# AnalogLedFader.net
KiCad netlist of a schematic drawn in EAGLE
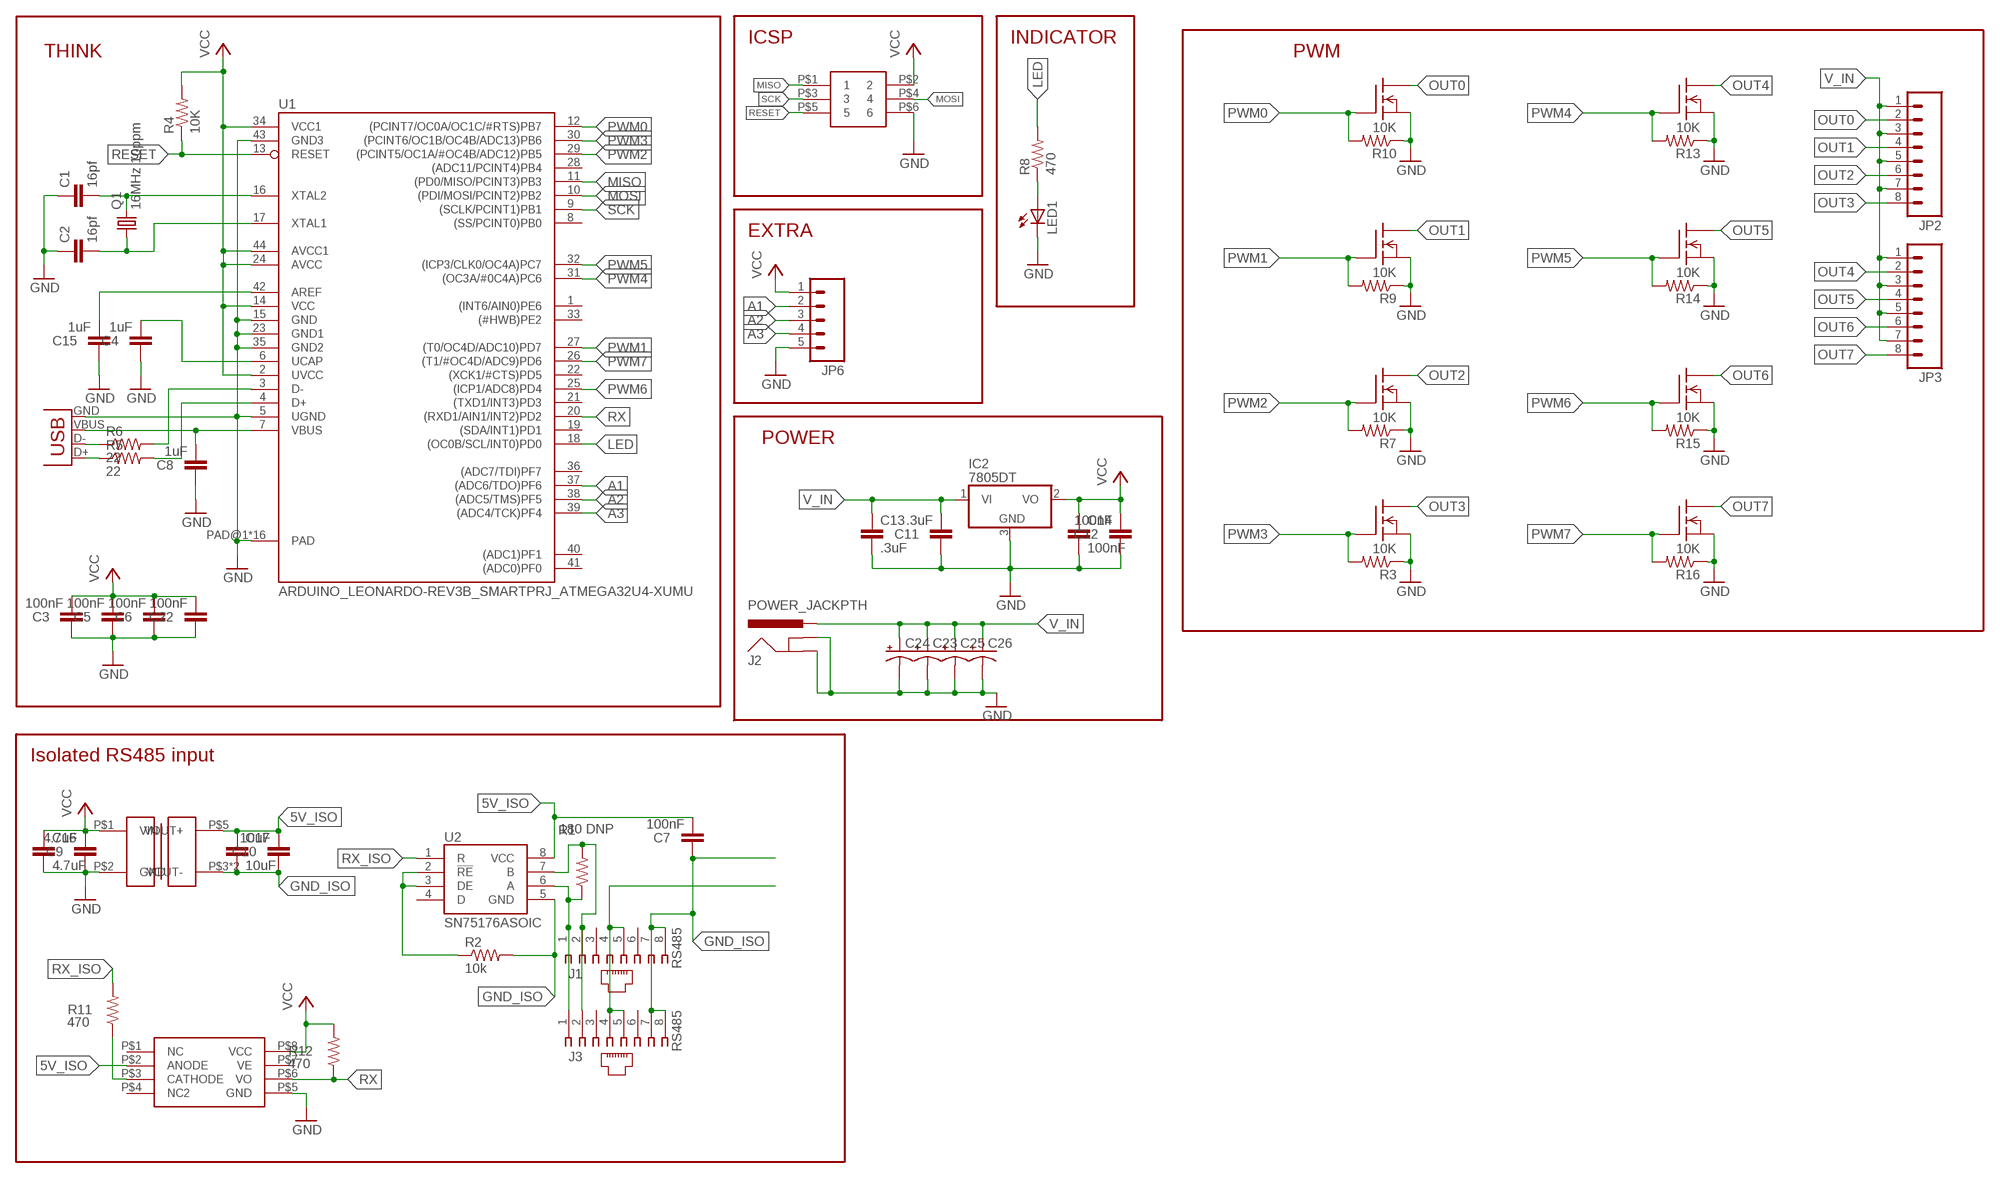
[diagram p0: schematic, sheet 1]

(export (version "E")
  (design (tool "Eeschema 10.0.6"))
  (components
    (comp (ref "C1")
      (value "16pf")
      (footprint "eagle-import:0805")
      (libsource (lib "eagle-import") (part "CAP0805"))
    )
    (comp (ref "C2")
      (value "16pf")
      (footprint "eagle-import:0805")
      (libsource (lib "eagle-import") (part "CAP0805"))
    )
    (comp (ref "C3")
      (value "100nF")
      (footprint "eagle-import:0805")
      (libsource (lib "eagle-import") (part "CAP0805"))
    )
    (comp (ref "C4")
      (value "1uF")
      (footprint "eagle-import:0805")
      (libsource (lib "eagle-import") (part "CAP0805"))
    )
    (comp (ref "C5")
      (value "100nF")
      (footprint "eagle-import:0805")
      (libsource (lib "eagle-import") (part "CAP0805"))
    )
    (comp (ref "C6")
      (value "100nF")
      (footprint "eagle-import:0805")
      (libsource (lib "eagle-import") (part "CAP0805"))
    )
    (comp (ref "C7")
      (value "100nF")
      (footprint "eagle-import:0805")
      (libsource (lib "eagle-import") (part "CAP0805"))
    )
    (comp (ref "C8")
      (value "1uF")
      (footprint "eagle-import:0805")
      (libsource (lib "eagle-import") (part "CAP0805"))
    )
    (comp (ref "C9")
      (value "4.7uF")
      (footprint "eagle-import:0805")
      (libsource (lib "eagle-import") (part "CAP0805"))
    )
    (comp (ref "C10")
      (value "10uF")
      (footprint "eagle-import:0805")
      (libsource (lib "eagle-import") (part "CAP0805"))
    )
    (comp (ref "C11")
      (value ".3uF")
      (footprint "eagle-import:0805")
      (libsource (lib "eagle-import") (part "CAP0805"))
    )
    (comp (ref "C12")
      (value "100nF")
      (footprint "eagle-import:0805")
      (libsource (lib "eagle-import") (part "CAP0805"))
    )
    (comp (ref "C13")
      (value ".3uF")
      (footprint "eagle-import:1210")
      (libsource (lib "eagle-import") (part "CAP1210"))
    )
    (comp (ref "C14")
      (value "100nF")
      (footprint "eagle-import:1210")
      (libsource (lib "eagle-import") (part "CAP1210"))
    )
    (comp (ref "C15")
      (value "1uF")
      (footprint "eagle-import:0805")
      (libsource (lib "eagle-import") (part "CAP0805"))
    )
    (comp (ref "C16")
      (value "4.7uF")
      (footprint "eagle-import:1210")
      (libsource (lib "eagle-import") (part "CAP1210"))
    )
    (comp (ref "C17")
      (value "10uF")
      (footprint "eagle-import:1210")
      (libsource (lib "eagle-import") (part "CAP1210"))
    )
    (comp (ref "C22")
      (value "100nF")
      (footprint "eagle-import:0805")
      (libsource (lib "eagle-import") (part "CAP0805"))
    )
    (comp (ref "C23")
      (value "CAP_POLE")
      (footprint "eagle-import:PANASONIC_E")
      (libsource (lib "eagle-import") (part "CAP_POLE"))
    )
    (comp (ref "C24")
      (value "CAP_POLE")
      (footprint "eagle-import:PANASONIC_E")
      (libsource (lib "eagle-import") (part "CAP_POLE"))
    )
    (comp (ref "C25")
      (value "CAP_POLE")
      (footprint "eagle-import:PANASONIC_E")
      (libsource (lib "eagle-import") (part "CAP_POLE"))
    )
    (comp (ref "C26")
      (value "CAP_POLE")
      (footprint "eagle-import:PANASONIC_E")
      (libsource (lib "eagle-import") (part "CAP_POLE"))
    )
    (comp (ref "IC2")
      (value "7805DT")
      (footprint "eagle-import:TO252")
      (libsource (lib "eagle-import") (part "78DT05"))
    )
    (comp (ref "J1")
      (value "RS485")
      (footprint "eagle-import:520426-4")
      (libsource (lib "eagle-import") (part "520426-4"))
    )
    (comp (ref "J2")
      (value "POWER_JACKPTH")
      (footprint "eagle-import:POWER_JACK_PTH")
      (libsource (lib "eagle-import") (part "POWER_JACKPTH"))
    )
    (comp (ref "J3")
      (value "RS485")
      (footprint "eagle-import:520426-4")
      (libsource (lib "eagle-import") (part "520426-4"))
    )
    (comp (ref "JP2")
      (value "M083.5MM-8")
      (footprint "eagle-import:SCREWTERMINAL-3.5MM-8")
      (libsource (lib "eagle-import") (part "M083.5MM-8"))
    )
    (comp (ref "JP3")
      (value "M083.5MM-8")
      (footprint "eagle-import:SCREWTERMINAL-3.5MM-8")
      (libsource (lib "eagle-import") (part "M083.5MM-8"))
    )
    (comp (ref "JP6")
      (value "M05PTH")
      (footprint "eagle-import:1X05")
      (libsource (lib "eagle-import") (part "M05PTH"))
    )
    (comp (ref "LED1")
      (value "LED5MM")
      (footprint "eagle-import:LED5MM")
      (libsource (lib "eagle-import") (part "LED5MM"))
    )
    (comp (ref "Q1")
      (value "16MHz 10ppm")
      (footprint "eagle-import:XS3225")
      (libsource (lib "eagle-import") (part "CRYSTAL"))
    )
    (comp (ref "R1")
      (value "180 DNP")
      (footprint "eagle-import:0805")
      (libsource (lib "eagle-import") (part "RESISTOR"))
    )
    (comp (ref "R2")
      (value "10k")
      (footprint "eagle-import:0805")
      (libsource (lib "eagle-import") (part "RESISTOR"))
    )
    (comp (ref "R3")
      (value "10K")
      (footprint "eagle-import:0805")
      (libsource (lib "eagle-import") (part "RESISTOR"))
    )
    (comp (ref "R4")
      (value "10K")
      (footprint "eagle-import:0805")
      (libsource (lib "eagle-import") (part "RESISTOR"))
    )
    (comp (ref "R5")
      (value "22")
      (footprint "eagle-import:0805")
      (libsource (lib "eagle-import") (part "RESISTOR"))
    )
    (comp (ref "R6")
      (value "22")
      (footprint "eagle-import:0805")
      (libsource (lib "eagle-import") (part "RESISTOR"))
    )
    (comp (ref "R7")
      (value "10K")
      (footprint "eagle-import:0805")
      (libsource (lib "eagle-import") (part "RESISTOR"))
    )
    (comp (ref "R8")
      (value "470")
      (footprint "eagle-import:0805")
      (libsource (lib "eagle-import") (part "RESISTOR"))
    )
    (comp (ref "R9")
      (value "10K")
      (footprint "eagle-import:0805")
      (libsource (lib "eagle-import") (part "RESISTOR"))
    )
    (comp (ref "R10")
      (value "10K")
      (footprint "eagle-import:0805")
      (libsource (lib "eagle-import") (part "RESISTOR"))
    )
    (comp (ref "R11")
      (value "470")
      (footprint "eagle-import:0805")
      (libsource (lib "eagle-import") (part "RESISTOR"))
    )
    (comp (ref "R12")
      (value "470")
      (footprint "eagle-import:0805")
      (libsource (lib "eagle-import") (part "RESISTOR"))
    )
    (comp (ref "R13")
      (value "10K")
      (footprint "eagle-import:0805")
      (libsource (lib "eagle-import") (part "RESISTOR"))
    )
    (comp (ref "R14")
      (value "10K")
      (footprint "eagle-import:0805")
      (libsource (lib "eagle-import") (part "RESISTOR"))
    )
    (comp (ref "R15")
      (value "10K")
      (footprint "eagle-import:0805")
      (libsource (lib "eagle-import") (part "RESISTOR"))
    )
    (comp (ref "R16")
      (value "10K")
      (footprint "eagle-import:0805")
      (libsource (lib "eagle-import") (part "RESISTOR"))
    )
    (comp (ref "U$1")
      (value "N_MOSFET")
      (footprint "eagle-import:TO252")
      (libsource (lib "eagle-import") (part "N_MOSFET"))
    )
    (comp (ref "U$2")
      (value "2X3HEADER")
      (footprint "eagle-import:2X3HEADER")
      (libsource (lib "eagle-import") (part "2X3HEADER"))
    )
    (comp (ref "U$3")
      (value "N_MOSFET")
      (footprint "eagle-import:TO252")
      (libsource (lib "eagle-import") (part "N_MOSFET"))
    )
    (comp (ref "U$4")
      (value "N_MOSFET")
      (footprint "eagle-import:TO252")
      (libsource (lib "eagle-import") (part "N_MOSFET"))
    )
    (comp (ref "U$5")
      (value "N_MOSFET")
      (footprint "eagle-import:TO252")
      (libsource (lib "eagle-import") (part "N_MOSFET"))
    )
    (comp (ref "U$6")
      (value "N_MOSFET")
      (footprint "eagle-import:TO252")
      (libsource (lib "eagle-import") (part "N_MOSFET"))
    )
    (comp (ref "U$7")
      (value "N_MOSFET")
      (footprint "eagle-import:TO252")
      (libsource (lib "eagle-import") (part "N_MOSFET"))
    )
    (comp (ref "U$8")
      (value "N_MOSFET")
      (footprint "eagle-import:TO252")
      (libsource (lib "eagle-import") (part "N_MOSFET"))
    )
    (comp (ref "U$9")
      (value "N_MOSFET")
      (footprint "eagle-import:TO252")
      (libsource (lib "eagle-import") (part "N_MOSFET"))
    )
    (comp (ref "U$10")
      (value "DC_DC_ISOLATED_0505")
      (footprint "eagle-import:IB_XLS-1W")
      (libsource (lib "eagle-import") (part "DC_DC_ISOLATED_0505"))
    )
    (comp (ref "U$12")
      (value "6N137")
      (footprint "eagle-import:8_SOIC")
      (libsource (lib "eagle-import") (part "6N137"))
    )
    (comp (ref "U1")
      (value "ARDUINO_LEONARDO-REV3B_SMARTPRJ_ATMEGA32U4-XUMU")
      (footprint "eagle-import:ARDUINO_LEONARDO-REV3B_SMARTPRJ_QFN44ML7X7")
      (libsource (lib "eagle-import") (part "ARDUINO_LEONARDO-REV3B_SMARTPRJ_ATMEGA32U4-XUMU"))
    )
    (comp (ref "U2")
      (value "SN75176ASOIC")
      (footprint "eagle-import:SO08")
      (libsource (lib "eagle-import") (part "SN75176ASOIC"))
    )
    (comp (ref "X1")
      (value "USBPTH")
      (footprint "eagle-import:USB-B-PTH")
      (libsource (lib "eagle-import") (part "USBPTH"))
    )
  )
  (nets
    (net (code "1") (name "5V_ISO") (class "Default")
      (node (ref "C10") (pin "2") (pinfunction "2_2") (pintype "passive"))
      (node (ref "C17") (pin "1") (pinfunction "1_1") (pintype "passive"))
      (node (ref "C7") (pin "2") (pinfunction "2_2") (pintype "passive"))
      (node (ref "U$10") (pin "P$5") (pinfunction "VOUT+_P$5") (pintype "power_in"))
      (node (ref "U$12") (pin "P$2") (pinfunction "ANODE_P$2") (pintype "bidirectional"))
      (node (ref "U2") (pin "8") (pinfunction "VCC_8") (pintype "bidirectional"))
    )
    (net (code "2") (name "A1") (class "Default")
      (node (ref "JP6") (pin "2") (pinfunction "2_2") (pintype "passive"))
      (node (ref "U1") (pin "37") (pinfunction "(ADC6/TDO)PF6_37") (pintype "bidirectional"))
    )
    (net (code "3") (name "A2") (class "Default")
      (node (ref "JP6") (pin "3") (pinfunction "3_3") (pintype "passive"))
      (node (ref "U1") (pin "38") (pinfunction "(ADC5/TMS)PF5_38") (pintype "bidirectional"))
    )
    (net (code "4") (name "A3") (class "Default")
      (node (ref "JP6") (pin "4") (pinfunction "4_4") (pintype "passive"))
      (node (ref "U1") (pin "39") (pinfunction "(ADC4/TCK)PF4_39") (pintype "bidirectional"))
    )
    (net (code "5") (name "GND") (class "Default")
      (node (ref "C1") (pin "1") (pinfunction "1_1") (pintype "passive"))
      (node (ref "C11") (pin "1") (pinfunction "1_1") (pintype "passive"))
      (node (ref "C12") (pin "1") (pinfunction "1_1") (pintype "passive"))
      (node (ref "C13") (pin "2") (pinfunction "2_2") (pintype "passive"))
      (node (ref "C14") (pin "2") (pinfunction "2_2") (pintype "passive"))
      (node (ref "C15") (pin "1") (pinfunction "1_1") (pintype "passive"))
      (node (ref "C16") (pin "2") (pinfunction "2_2") (pintype "passive"))
      (node (ref "C2") (pin "1") (pinfunction "1_1") (pintype "passive"))
      (node (ref "C22") (pin "1") (pinfunction "1_1") (pintype "passive"))
      (node (ref "C23") (pin "-") (pinfunction "-_-") (pintype "passive"))
      (node (ref "C24") (pin "-") (pinfunction "-_-") (pintype "passive"))
      (node (ref "C25") (pin "-") (pinfunction "-_-") (pintype "passive"))
      (node (ref "C26") (pin "-") (pinfunction "-_-") (pintype "passive"))
      (node (ref "C3") (pin "1") (pinfunction "1_1") (pintype "passive"))
      (node (ref "C4") (pin "1") (pinfunction "1_1") (pintype "passive"))
      (node (ref "C5") (pin "1") (pinfunction "1_1") (pintype "passive"))
      (node (ref "C6") (pin "1") (pinfunction "1_1") (pintype "passive"))
      (node (ref "C8") (pin "1") (pinfunction "1_1") (pintype "passive"))
      (node (ref "C9") (pin "1") (pinfunction "1_1") (pintype "passive"))
      (node (ref "IC2") (pin "3") (pinfunction "GND_3") (pintype "passive"))
      (node (ref "J2") (pin "GND") (pinfunction "GND_GND") (pintype "bidirectional"))
      (node (ref "J2") (pin "GNDBREAK") (pinfunction "GNDBREAK_GNDBREAK") (pintype "bidirectional"))
      (node (ref "JP6") (pin "5") (pinfunction "5_5") (pintype "passive"))
      (node (ref "LED1") (pin "K") (pinfunction "C_K") (pintype "passive"))
      (node (ref "R10") (pin "1") (pinfunction "1_1") (pintype "passive"))
      (node (ref "R13") (pin "1") (pinfunction "1_1") (pintype "passive"))
      (node (ref "R14") (pin "1") (pinfunction "1_1") (pintype "passive"))
      (node (ref "R15") (pin "1") (pinfunction "1_1") (pintype "passive"))
      (node (ref "R16") (pin "1") (pinfunction "1_1") (pintype "passive"))
      (node (ref "R3") (pin "1") (pinfunction "1_1") (pintype "passive"))
      (node (ref "R7") (pin "1") (pinfunction "1_1") (pintype "passive"))
      (node (ref "R9") (pin "1") (pinfunction "1_1") (pintype "passive"))
      (node (ref "U$1") (pin "P$2") (pinfunction "S_P$2") (pintype "bidirectional"))
      (node (ref "U$10") (pin "P$2") (pinfunction "GND_P$2") (pintype "power_in"))
      (node (ref "U$12") (pin "P$5") (pinfunction "GND_P$5") (pintype "bidirectional"))
      (node (ref "U$2") (pin "P$6") (pinfunction "6_P$6") (pintype "bidirectional"))
      (node (ref "U$3") (pin "P$2") (pinfunction "S_P$2") (pintype "bidirectional"))
      (node (ref "U$4") (pin "P$2") (pinfunction "S_P$2") (pintype "bidirectional"))
      (node (ref "U$5") (pin "P$2") (pinfunction "S_P$2") (pintype "bidirectional"))
      (node (ref "U$6") (pin "P$2") (pinfunction "S_P$2") (pintype "bidirectional"))
      (node (ref "U$7") (pin "P$2") (pinfunction "S_P$2") (pintype "bidirectional"))
      (node (ref "U$8") (pin "P$2") (pinfunction "S_P$2") (pintype "bidirectional"))
      (node (ref "U$9") (pin "P$2") (pinfunction "S_P$2") (pintype "bidirectional"))
      (node (ref "U1") (pin "15") (pinfunction "GND_15") (pintype "power_in"))
      (node (ref "U1") (pin "23") (pinfunction "GND1_23") (pintype "power_in"))
      (node (ref "U1") (pin "35") (pinfunction "GND2_35") (pintype "power_in"))
      (node (ref "U1") (pin "43") (pinfunction "GND3_43") (pintype "power_in"))
      (node (ref "U1") (pin "5") (pinfunction "UGND_5") (pintype "power_in"))
      (node (ref "U1") (pin "PAD@1") (pinfunction "PAD_PAD@1") (pintype "power_in"))
      (node (ref "U1") (pin "PAD@10") (pinfunction "PAD_PAD@10") (pintype "power_in"))
      (node (ref "U1") (pin "PAD@11") (pinfunction "PAD_PAD@11") (pintype "power_in"))
      (node (ref "U1") (pin "PAD@12") (pinfunction "PAD_PAD@12") (pintype "power_in"))
      (node (ref "U1") (pin "PAD@13") (pinfunction "PAD_PAD@13") (pintype "power_in"))
      (node (ref "U1") (pin "PAD@14") (pinfunction "PAD_PAD@14") (pintype "power_in"))
      (node (ref "U1") (pin "PAD@15") (pinfunction "PAD_PAD@15") (pintype "power_in"))
      (node (ref "U1") (pin "PAD@16") (pinfunction "PAD_PAD@16") (pintype "power_in"))
      (node (ref "U1") (pin "PAD@2") (pinfunction "PAD_PAD@2") (pintype "power_in"))
      (node (ref "U1") (pin "PAD@3") (pinfunction "PAD_PAD@3") (pintype "power_in"))
      (node (ref "U1") (pin "PAD@4") (pinfunction "PAD_PAD@4") (pintype "power_in"))
      (node (ref "U1") (pin "PAD@5") (pinfunction "PAD_PAD@5") (pintype "power_in"))
      (node (ref "U1") (pin "PAD@6") (pinfunction "PAD_PAD@6") (pintype "power_in"))
      (node (ref "U1") (pin "PAD@7") (pinfunction "PAD_PAD@7") (pintype "power_in"))
      (node (ref "U1") (pin "PAD@8") (pinfunction "PAD_PAD@8") (pintype "power_in"))
      (node (ref "U1") (pin "PAD@9") (pinfunction "PAD_PAD@9") (pintype "power_in"))
      (node (ref "X1") (pin "GND") (pinfunction "GND_GND") (pintype "bidirectional"))
    )
    (net (code "6") (name "GND_ISO") (class "Default")
      (node (ref "C10") (pin "1") (pinfunction "1_1") (pintype "passive"))
      (node (ref "C17") (pin "2") (pinfunction "2_2") (pintype "passive"))
      (node (ref "C7") (pin "1") (pinfunction "1_1") (pintype "passive"))
      (node (ref "J1") (pin "7") (pinfunction "7_7") (pintype "passive"))
      (node (ref "J1") (pin "8") (pinfunction "8_8") (pintype "passive"))
      (node (ref "J3") (pin "7") (pinfunction "7_7") (pintype "passive"))
      (node (ref "J3") (pin "8") (pinfunction "8_8") (pintype "passive"))
      (node (ref "R2") (pin "2") (pinfunction "2_2") (pintype "passive"))
      (node (ref "U$10") (pin "P$3") (pinfunction "VOUT-_P$3") (pintype "power_in"))
      (node (ref "U$10") (pin "P$4") (pinfunction "VOUT-_P$4") (pintype "power_in"))
      (node (ref "U2") (pin "5") (pinfunction "GND_5") (pintype "bidirectional"))
    )
    (net (code "7") (name "LED") (class "Default")
      (node (ref "R8") (pin "2") (pinfunction "2_2") (pintype "passive"))
      (node (ref "U1") (pin "18") (pinfunction "(OC0B/SCL/INT0)PD0_18") (pintype "bidirectional"))
    )
    (net (code "8") (name "MISO") (class "Default")
      (node (ref "U$2") (pin "P$1") (pinfunction "1_P$1") (pintype "bidirectional"))
      (node (ref "U1") (pin "11") (pinfunction "(PD0/MISO/PCINT3)PB3_11") (pintype "bidirectional"))
    )
    (net (code "9") (name "MOSI") (class "Default")
      (node (ref "U$2") (pin "P$4") (pinfunction "4_P$4") (pintype "bidirectional"))
      (node (ref "U1") (pin "10") (pinfunction "(PDI/MOSI/PCINT2)PB2_10") (pintype "bidirectional"))
    )
    (net (code "10") (name "Net-(J1-Pad4)") (class "Default")
      (node (ref "J1") (pin "4") (pinfunction "4_4") (pintype "passive"))
      (node (ref "J1") (pin "5") (pinfunction "5_5") (pintype "passive"))
      (node (ref "J3") (pin "4") (pinfunction "4_4") (pintype "passive"))
      (node (ref "J3") (pin "5") (pinfunction "5_5") (pintype "passive"))
    )
    (net (code "11") (name "Net-(LED1-PadA)") (class "Default")
      (node (ref "LED1") (pin "A") (pinfunction "A_A") (pintype "passive"))
      (node (ref "R8") (pin "1") (pinfunction "1_1") (pintype "passive"))
    )
    (net (code "12") (name "Net-(Q1-1)") (class "Default")
      (node (ref "C2") (pin "2") (pinfunction "2_2") (pintype "passive"))
      (node (ref "Q1") (pin "P$1") (pinfunction "1_P$1") (pintype "passive"))
      (node (ref "U1") (pin "17") (pinfunction "XTAL1_17") (pintype "bidirectional"))
    )
    (net (code "13") (name "Net-(Q1-2)") (class "Default")
      (node (ref "C1") (pin "2") (pinfunction "2_2") (pintype "passive"))
      (node (ref "Q1") (pin "P$3") (pinfunction "2_P$3") (pintype "passive"))
      (node (ref "U1") (pin "16") (pinfunction "XTAL2_16") (pintype "bidirectional"))
    )
    (net (code "14") (name "Net-(R5-Pad1)") (class "Default")
      (node (ref "R5") (pin "1") (pinfunction "1_1") (pintype "passive"))
      (node (ref "X1") (pin "D+") (pinfunction "D+_D+") (pintype "bidirectional"))
    )
    (net (code "15") (name "Net-(R6-Pad1)") (class "Default")
      (node (ref "R6") (pin "1") (pinfunction "1_1") (pintype "passive"))
      (node (ref "X1") (pin "D-") (pinfunction "D-_D-") (pintype "bidirectional"))
    )
    (net (code "16") (name "Net-(U$12-CATHODE)") (class "Default")
      (node (ref "R11") (pin "1") (pinfunction "1_1") (pintype "passive"))
      (node (ref "U$12") (pin "P$3") (pinfunction "CATHODE_P$3") (pintype "bidirectional"))
    )
    (net (code "17") (name "Net-(U1-AREF)") (class "Default")
      (node (ref "C15") (pin "2") (pinfunction "2_2") (pintype "passive"))
      (node (ref "U1") (pin "42") (pinfunction "AREF_42") (pintype "power_in"))
    )
    (net (code "18") (name "Net-(U1-D+)") (class "Default")
      (node (ref "R5") (pin "2") (pinfunction "2_2") (pintype "passive"))
      (node (ref "U1") (pin "4") (pinfunction "D+_4") (pintype "bidirectional"))
    )
    (net (code "19") (name "Net-(U1-D-)") (class "Default")
      (node (ref "R6") (pin "2") (pinfunction "2_2") (pintype "passive"))
      (node (ref "U1") (pin "3") (pinfunction "D-_3") (pintype "bidirectional"))
    )
    (net (code "20") (name "Net-(U1-UCAP)") (class "Default")
      (node (ref "C4") (pin "2") (pinfunction "2_2") (pintype "passive"))
      (node (ref "U1") (pin "6") (pinfunction "UCAP_6") (pintype "passive"))
    )
    (net (code "21") (name "Net-(U1-VBUS)") (class "Default")
      (node (ref "C8") (pin "2") (pinfunction "2_2") (pintype "passive"))
      (node (ref "U1") (pin "7") (pinfunction "VBUS_7") (pintype "input"))
      (node (ref "X1") (pin "VBUS") (pinfunction "VBUS_VBUS") (pintype "bidirectional"))
    )
    (net (code "22") (name "Net-(U2-A)") (class "Default")
      (node (ref "J1") (pin "1") (pinfunction "1_1") (pintype "passive"))
      (node (ref "J3") (pin "1") (pinfunction "1_1") (pintype "passive"))
      (node (ref "R1") (pin "1") (pinfunction "1_1") (pintype "passive"))
      (node (ref "U2") (pin "6") (pinfunction "A_6") (pintype "bidirectional"))
    )
    (net (code "23") (name "Net-(U2-B)") (class "Default")
      (node (ref "J1") (pin "2") (pinfunction "2_2") (pintype "passive"))
      (node (ref "J3") (pin "2") (pinfunction "2_2") (pintype "passive"))
      (node (ref "R1") (pin "2") (pinfunction "2_2") (pintype "passive"))
      (node (ref "U2") (pin "7") (pinfunction "B_7") (pintype "bidirectional"))
    )
    (net (code "24") (name "Net-(U2-DE)") (class "Default")
      (node (ref "R2") (pin "1") (pinfunction "1_1") (pintype "passive"))
      (node (ref "U2") (pin "2") (pinfunction "~{RE}_2") (pintype "bidirectional"))
      (node (ref "U2") (pin "3") (pinfunction "DE_3") (pintype "bidirectional"))
    )
    (net (code "25") (name "OUT0") (class "Default")
      (node (ref "JP2") (pin "2") (pinfunction "2_2") (pintype "passive"))
      (node (ref "U$1") (pin "P$3") (pinfunction "D_P$3") (pintype "bidirectional"))
    )
    (net (code "26") (name "OUT1") (class "Default")
      (node (ref "JP2") (pin "4") (pinfunction "4_4") (pintype "passive"))
      (node (ref "U$3") (pin "P$3") (pinfunction "D_P$3") (pintype "bidirectional"))
    )
    (net (code "27") (name "OUT2") (class "Default")
      (node (ref "JP2") (pin "6") (pinfunction "6_6") (pintype "passive"))
      (node (ref "U$4") (pin "P$3") (pinfunction "D_P$3") (pintype "bidirectional"))
    )
    (net (code "28") (name "OUT3") (class "Default")
      (node (ref "JP2") (pin "8") (pinfunction "8_8") (pintype "passive"))
      (node (ref "U$5") (pin "P$3") (pinfunction "D_P$3") (pintype "bidirectional"))
    )
    (net (code "29") (name "OUT4") (class "Default")
      (node (ref "JP3") (pin "2") (pinfunction "2_2") (pintype "passive"))
      (node (ref "U$6") (pin "P$3") (pinfunction "D_P$3") (pintype "bidirectional"))
    )
    (net (code "30") (name "OUT5") (class "Default")
      (node (ref "JP3") (pin "4") (pinfunction "4_4") (pintype "passive"))
      (node (ref "U$7") (pin "P$3") (pinfunction "D_P$3") (pintype "bidirectional"))
    )
    (net (code "31") (name "OUT6") (class "Default")
      (node (ref "JP3") (pin "6") (pinfunction "6_6") (pintype "passive"))
      (node (ref "U$8") (pin "P$3") (pinfunction "D_P$3") (pintype "bidirectional"))
    )
    (net (code "32") (name "OUT7") (class "Default")
      (node (ref "JP3") (pin "8") (pinfunction "8_8") (pintype "passive"))
      (node (ref "U$9") (pin "P$3") (pinfunction "D_P$3") (pintype "bidirectional"))
    )
    (net (code "33") (name "PWM0") (class "Default")
      (node (ref "R10") (pin "2") (pinfunction "2_2") (pintype "passive"))
      (node (ref "U$1") (pin "P$1") (pinfunction "G_P$1") (pintype "bidirectional"))
      (node (ref "U1") (pin "12") (pinfunction "(PCINT7/OC0A/OC1C/#RTS)PB7_12") (pintype "bidirectional"))
    )
    (net (code "34") (name "PWM1") (class "Default")
      (node (ref "R9") (pin "2") (pinfunction "2_2") (pintype "passive"))
      (node (ref "U$3") (pin "P$1") (pinfunction "G_P$1") (pintype "bidirectional"))
      (node (ref "U1") (pin "27") (pinfunction "(T0/OC4D/ADC10)PD7_27") (pintype "bidirectional"))
    )
    (net (code "35") (name "PWM2") (class "Default")
      (node (ref "R7") (pin "2") (pinfunction "2_2") (pintype "passive"))
      (node (ref "U$4") (pin "P$1") (pinfunction "G_P$1") (pintype "bidirectional"))
      (node (ref "U1") (pin "29") (pinfunction "(PCINT5/OC1A/#OC4B/ADC12)PB5_29") (pintype "bidirectional"))
    )
    (net (code "36") (name "PWM3") (class "Default")
      (node (ref "R3") (pin "2") (pinfunction "2_2") (pintype "passive"))
      (node (ref "U$5") (pin "P$1") (pinfunction "G_P$1") (pintype "bidirectional"))
      (node (ref "U1") (pin "30") (pinfunction "(PCINT6/OC1B/OC4B/ADC13)PB6_30") (pintype "bidirectional"))
    )
    (net (code "37") (name "PWM4") (class "Default")
      (node (ref "R13") (pin "2") (pinfunction "2_2") (pintype "passive"))
      (node (ref "U$6") (pin "P$1") (pinfunction "G_P$1") (pintype "bidirectional"))
      (node (ref "U1") (pin "31") (pinfunction "(OC3A/#0C4A)PC6_31") (pintype "bidirectional"))
    )
    (net (code "38") (name "PWM5") (class "Default")
      (node (ref "R14") (pin "2") (pinfunction "2_2") (pintype "passive"))
      (node (ref "U$7") (pin "P$1") (pinfunction "G_P$1") (pintype "bidirectional"))
      (node (ref "U1") (pin "32") (pinfunction "(ICP3/CLK0/OC4A)PC7_32") (pintype "bidirectional"))
    )
    (net (code "39") (name "PWM6") (class "Default")
      (node (ref "R15") (pin "2") (pinfunction "2_2") (pintype "passive"))
      (node (ref "U$8") (pin "P$1") (pinfunction "G_P$1") (pintype "bidirectional"))
      (node (ref "U1") (pin "25") (pinfunction "(ICP1/ADC8)PD4_25") (pintype "bidirectional"))
    )
    (net (code "40") (name "PWM7") (class "Default")
      (node (ref "R16") (pin "2") (pinfunction "2_2") (pintype "passive"))
      (node (ref "U$9") (pin "P$1") (pinfunction "G_P$1") (pintype "bidirectional"))
      (node (ref "U1") (pin "26") (pinfunction "(T1/#OC4D/ADC9)PD6_26") (pintype "bidirectional"))
    )
    (net (code "41") (name "RESET") (class "Default")
      (node (ref "R4") (pin "1") (pinfunction "1_1") (pintype "passive"))
      (node (ref "U$2") (pin "P$5") (pinfunction "5_P$5") (pintype "bidirectional"))
      (node (ref "U1") (pin "13") (pinfunction "RESET_13") (pintype "input"))
    )
    (net (code "42") (name "RX") (class "Default")
      (node (ref "R12") (pin "1") (pinfunction "1_1") (pintype "passive"))
      (node (ref "U$12") (pin "P$6") (pinfunction "VO_P$6") (pintype "bidirectional"))
      (node (ref "U1") (pin "20") (pinfunction "(RXD1/AIN1/INT2)PD2_20") (pintype "bidirectional"))
    )
    (net (code "43") (name "RX_ISO") (class "Default")
      (node (ref "R11") (pin "2") (pinfunction "2_2") (pintype "passive"))
      (node (ref "U2") (pin "1") (pinfunction "R_1") (pintype "bidirectional"))
    )
    (net (code "44") (name "SCK") (class "Default")
      (node (ref "U$2") (pin "P$3") (pinfunction "3_P$3") (pintype "bidirectional"))
      (node (ref "U1") (pin "9") (pinfunction "(SCLK/PCINT1)PB1_9") (pintype "bidirectional"))
    )
    (net (code "45") (name "VCC") (class "Default")
      (node (ref "C12") (pin "2") (pinfunction "2_2") (pintype "passive"))
      (node (ref "C14") (pin "1") (pinfunction "1_1") (pintype "passive"))
      (node (ref "C16") (pin "1") (pinfunction "1_1") (pintype "passive"))
      (node (ref "C22") (pin "2") (pinfunction "2_2") (pintype "passive"))
      (node (ref "C3") (pin "2") (pinfunction "2_2") (pintype "passive"))
      (node (ref "C5") (pin "2") (pinfunction "2_2") (pintype "passive"))
      (node (ref "C6") (pin "2") (pinfunction "2_2") (pintype "passive"))
      (node (ref "C9") (pin "2") (pinfunction "2_2") (pintype "passive"))
      (node (ref "IC2") (pin "2") (pinfunction "VO_2") (pintype "passive"))
      (node (ref "JP6") (pin "1") (pinfunction "1_1") (pintype "passive"))
      (node (ref "R12") (pin "2") (pinfunction "2_2") (pintype "passive"))
      (node (ref "R4") (pin "2") (pinfunction "2_2") (pintype "passive"))
      (node (ref "U$10") (pin "P$1") (pinfunction "VIN_P$1") (pintype "power_in"))
      (node (ref "U$12") (pin "P$8") (pinfunction "VCC_P$8") (pintype "bidirectional"))
      (node (ref "U$2") (pin "P$2") (pinfunction "2_P$2") (pintype "bidirectional"))
      (node (ref "U1") (pin "14") (pinfunction "VCC_14") (pintype "power_in"))
      (node (ref "U1") (pin "2") (pinfunction "UVCC_2") (pintype "power_in"))
      (node (ref "U1") (pin "24") (pinfunction "AVCC_24") (pintype "power_in"))
      (node (ref "U1") (pin "34") (pinfunction "VCC1_34") (pintype "power_in"))
      (node (ref "U1") (pin "44") (pinfunction "AVCC1_44") (pintype "power_in"))
    )
    (net (code "46") (name "V_IN") (class "Default")
      (node (ref "C11") (pin "2") (pinfunction "2_2") (pintype "passive"))
      (node (ref "C13") (pin "1") (pinfunction "1_1") (pintype "passive"))
      (node (ref "C23") (pin "+") (pinfunction "+_+") (pintype "passive"))
      (node (ref "C24") (pin "+") (pinfunction "+_+") (pintype "passive"))
      (node (ref "C25") (pin "+") (pinfunction "+_+") (pintype "passive"))
      (node (ref "C26") (pin "+") (pinfunction "+_+") (pintype "passive"))
      (node (ref "IC2") (pin "1") (pinfunction "VI_1") (pintype "input"))
      (node (ref "J2") (pin "PWR") (pinfunction "PWR_PWR") (pintype "bidirectional"))
      (node (ref "JP2") (pin "1") (pinfunction "1_1") (pintype "passive"))
      (node (ref "JP2") (pin "3") (pinfunction "3_3") (pintype "passive"))
      (node (ref "JP2") (pin "5") (pinfunction "5_5") (pintype "passive"))
      (node (ref "JP2") (pin "7") (pinfunction "7_7") (pintype "passive"))
      (node (ref "JP3") (pin "1") (pinfunction "1_1") (pintype "passive"))
      (node (ref "JP3") (pin "3") (pinfunction "3_3") (pintype "passive"))
      (node (ref "JP3") (pin "5") (pinfunction "5_5") (pintype "passive"))
      (node (ref "JP3") (pin "7") (pinfunction "7_7") (pintype "passive"))
    )
    (net (code "47") (name "unconnected-(J1-Pad3)") (class "Default")
      (node (ref "J1") (pin "3") (pinfunction "3_3") (pintype "passive"))
    )
    (net (code "48") (name "unconnected-(J1-Pad6)") (class "Default")
      (node (ref "J1") (pin "6") (pinfunction "6_6") (pintype "passive"))
    )
    (net (code "49") (name "unconnected-(J3-Pad3)") (class "Default")
      (node (ref "J3") (pin "3") (pinfunction "3_3") (pintype "passive"))
    )
    (net (code "50") (name "unconnected-(J3-Pad6)") (class "Default")
      (node (ref "J3") (pin "6") (pinfunction "6_6") (pintype "passive"))
    )
    (net (code "51") (name "unconnected-(U$12-NC-PadP$1)") (class "Default")
      (node (ref "U$12") (pin "P$1") (pinfunction "NC_P$1") (pintype "bidirectional"))
    )
    (net (code "52") (name "unconnected-(U$12-NC2-PadP$4)") (class "Default")
      (node (ref "U$12") (pin "P$4") (pinfunction "NC2_P$4") (pintype "bidirectional"))
    )
    (net (code "53") (name "unconnected-(U$12-VE-PadP$7)") (class "Default")
      (node (ref "U$12") (pin "P$7") (pinfunction "VE_P$7") (pintype "bidirectional"))
    )
    (net (code "54") (name "unconnected-(U1-(#HWB)PE2-Pad33)") (class "Default")
      (node (ref "U1") (pin "33") (pinfunction "(#HWB)PE2_33") (pintype "bidirectional"))
    )
    (net (code "55") (name "unconnected-(U1-(ADC0)PF0-Pad41)") (class "Default")
      (node (ref "U1") (pin "41") (pinfunction "(ADC0)PF0_41") (pintype "bidirectional"))
    )
    (net (code "56") (name "unconnected-(U1-(ADC1)PF1-Pad40)") (class "Default")
      (node (ref "U1") (pin "40") (pinfunction "(ADC1)PF1_40") (pintype "bidirectional"))
    )
    (net (code "57") (name "unconnected-(U1-(ADC7{slash}TDI)PF7-Pad36)") (class "Default")
      (node (ref "U1") (pin "36") (pinfunction "(ADC7/TDI)PF7_36") (pintype "bidirectional"))
    )
    (net (code "58") (name "unconnected-(U1-(ADC11{slash}PCINT4)PB4-Pad28)") (class "Default")
      (node (ref "U1") (pin "28") (pinfunction "(ADC11/PCINT4)PB4_28") (pintype "bidirectional"))
    )
    (net (code "59") (name "unconnected-(U1-(INT6{slash}AIN0)PE6-Pad1)") (class "Default")
      (node (ref "U1") (pin "1") (pinfunction "(INT6/AIN0)PE6_1") (pintype "bidirectional"))
    )
    (net (code "60") (name "unconnected-(U1-(SDA{slash}INT1)PD1-Pad19)") (class "Default")
      (node (ref "U1") (pin "19") (pinfunction "(SDA/INT1)PD1_19") (pintype "bidirectional"))
    )
    (net (code "61") (name "unconnected-(U1-(SS{slash}PCINT0)PB0-Pad8)") (class "Default")
      (node (ref "U1") (pin "8") (pinfunction "(SS/PCINT0)PB0_8") (pintype "bidirectional"))
    )
    (net (code "62") (name "unconnected-(U1-(TXD1{slash}INT3)PD3-Pad21)") (class "Default")
      (node (ref "U1") (pin "21") (pinfunction "(TXD1/INT3)PD3_21") (pintype "bidirectional"))
    )
    (net (code "63") (name "unconnected-(U1-(XCK1{slash}#CTS)PD5-Pad22)") (class "Default")
      (node (ref "U1") (pin "22") (pinfunction "(XCK1/#CTS)PD5_22") (pintype "bidirectional"))
    )
    (net (code "64") (name "unconnected-(U2-D-Pad4)") (class "Default")
      (node (ref "U2") (pin "4") (pinfunction "D_4") (pintype "bidirectional"))
    )
  )
)
